# X-DO10_RFID_LED_V1_0_1.net
KiCad netlist of a schematic drawn in Altium Designer
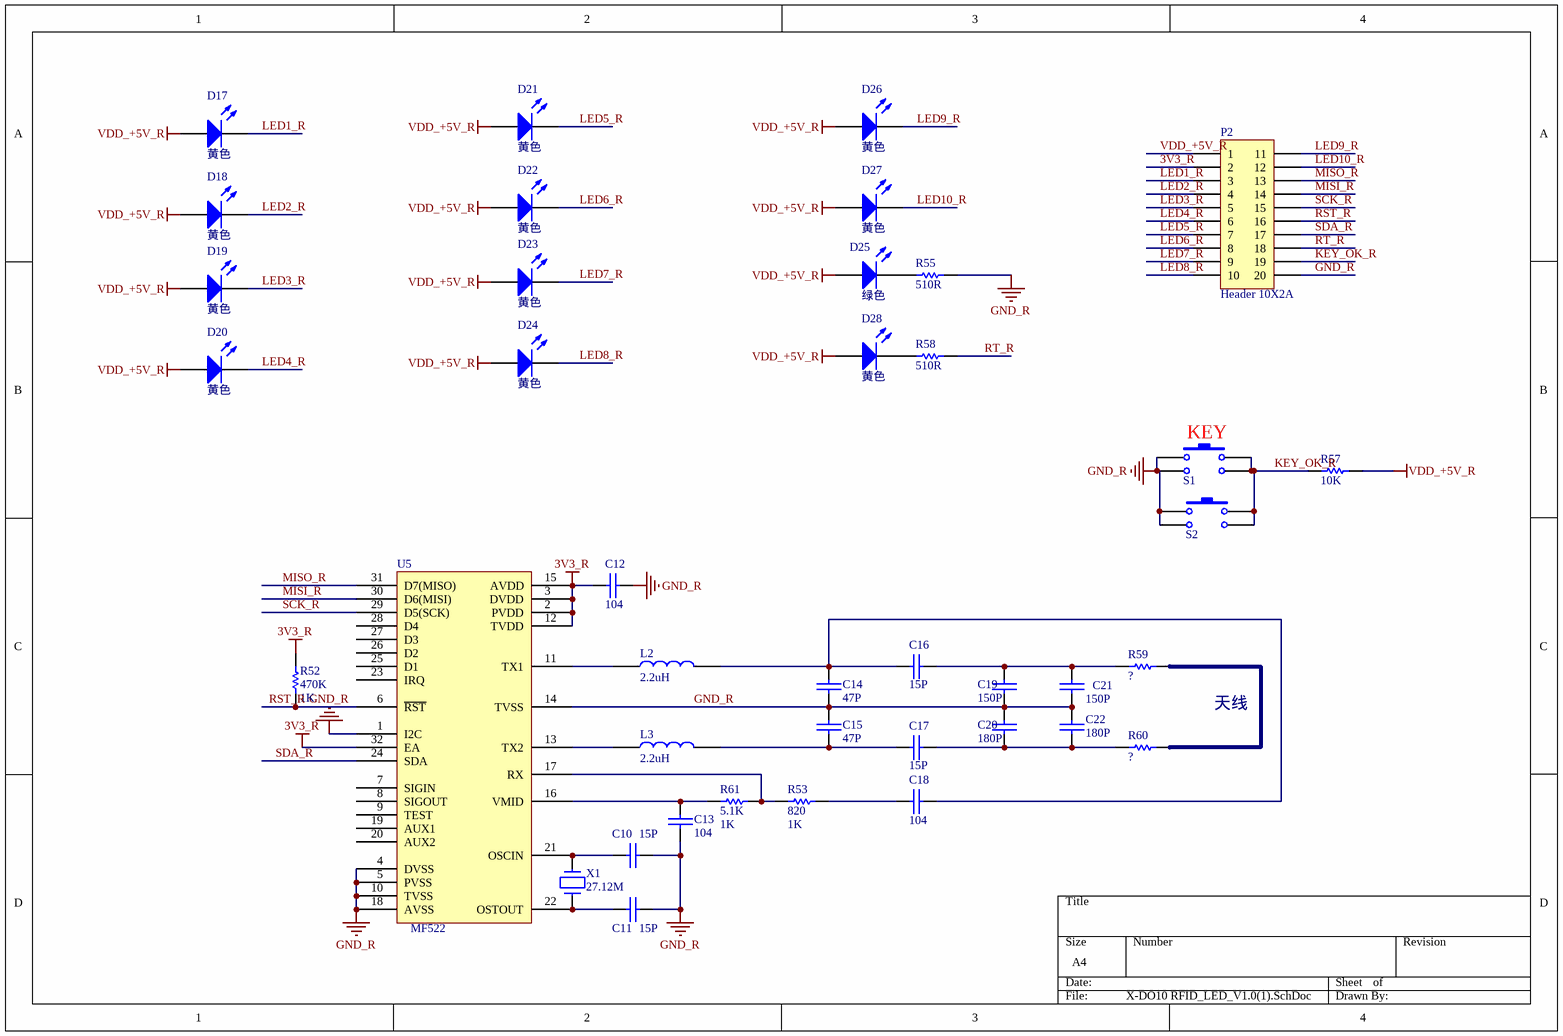
[diagram p0: X-DO10 RFID_LED_V1.0(1).SchDoc]

(export (version "E")
  (design (tool "Eeschema 10.0.6"))
  (components
    (comp (ref "C10")
      (value "15P")
      (footprint "c0603")
      (description "Capacitor")
      (libsource (lib "*") (part "CAP"))
    )
    (comp (ref "C11")
      (value "15P")
      (footprint "c0603")
      (description "Capacitor")
      (libsource (lib "*") (part "CAP"))
    )
    (comp (ref "C12")
      (value "104")
      (footprint "c0603")
      (description "Capacitor")
      (libsource (lib "*") (part "CAP"))
    )
    (comp (ref "C13")
      (value "104")
      (footprint "c0603")
      (description "Capacitor")
      (libsource (lib "*") (part "CAP"))
    )
    (comp (ref "C14")
      (value "47P")
      (footprint "c0603")
      (description "Capacitor")
      (libsource (lib "*") (part "CAP"))
    )
    (comp (ref "C15")
      (value "47P")
      (footprint "c0603")
      (description "Capacitor")
      (libsource (lib "*") (part "CAP"))
    )
    (comp (ref "C16")
      (value "15P")
      (footprint "c0603")
      (description "Capacitor")
      (libsource (lib "*") (part "CAP"))
    )
    (comp (ref "C17")
      (value "15P")
      (footprint "c0603")
      (description "Capacitor")
      (libsource (lib "*") (part "CAP"))
    )
    (comp (ref "C18")
      (value "104")
      (footprint "c0603")
      (description "Capacitor")
      (libsource (lib "*") (part "CAP"))
    )
    (comp (ref "C19")
      (value "150P")
      (footprint "c0603")
      (description "Capacitor")
      (libsource (lib "*") (part "CAP"))
    )
    (comp (ref "C20")
      (value "180P")
      (footprint "c0603")
      (description "Capacitor")
      (libsource (lib "*") (part "CAP"))
    )
    (comp (ref "C21")
      (value "150P")
      (footprint "c0603")
      (description "Capacitor")
      (libsource (lib "*") (part "CAP"))
    )
    (comp (ref "C22")
      (value "180P")
      (footprint "c0603")
      (description "Capacitor")
      (libsource (lib "*") (part "CAP"))
    )
    (comp (ref "D17")
      (value "黄色")
      (footprint "LED-2.54-3")
      (description "Typical INFRARED GaAs LED")
      (fields (field (name "ALTIUM_UNNAMED_1") "黄色"))
      (libsource (lib "*") (part "LED0"))
    )
    (comp (ref "D18")
      (value "黄色")
      (footprint "LED-2.54-3")
      (description "Typical INFRARED GaAs LED")
      (fields (field (name "ALTIUM_UNNAMED_1") "黄色"))
      (libsource (lib "*") (part "LED0"))
    )
    (comp (ref "D19")
      (value "黄色")
      (footprint "LED-2.54-3")
      (description "Typical INFRARED GaAs LED")
      (fields (field (name "ALTIUM_UNNAMED_1") "黄色"))
      (libsource (lib "*") (part "LED0"))
    )
    (comp (ref "D20")
      (value "黄色")
      (footprint "LED-2.54-3")
      (description "Typical INFRARED GaAs LED")
      (fields (field (name "ALTIUM_UNNAMED_1") "黄色"))
      (libsource (lib "*") (part "LED0"))
    )
    (comp (ref "D21")
      (value "黄色")
      (footprint "LED-2.54-3")
      (description "Typical INFRARED GaAs LED")
      (fields (field (name "ALTIUM_UNNAMED_1") "黄色"))
      (libsource (lib "*") (part "LED0"))
    )
    (comp (ref "D22")
      (value "黄色")
      (footprint "LED-2.54-3")
      (description "Typical INFRARED GaAs LED")
      (fields (field (name "ALTIUM_UNNAMED_1") "黄色"))
      (libsource (lib "*") (part "LED0"))
    )
    (comp (ref "D23")
      (value "黄色")
      (footprint "LED-2.54-3")
      (description "Typical INFRARED GaAs LED")
      (fields (field (name "ALTIUM_UNNAMED_1") "黄色"))
      (libsource (lib "*") (part "LED0"))
    )
    (comp (ref "D24")
      (value "黄色")
      (footprint "LED-2.54-3")
      (description "Typical INFRARED GaAs LED")
      (fields (field (name "ALTIUM_UNNAMED_1") "黄色"))
      (libsource (lib "*") (part "LED0"))
    )
    (comp (ref "D25")
      (value "红色")
      (footprint "LED-2.54-3")
      (description "Typical INFRARED GaAs LED")
      (fields (field (name "ALTIUM_UNNAMED_1") "绿色"))
      (libsource (lib "*") (part "LED0"))
    )
    (comp (ref "D26")
      (value "黄色")
      (footprint "LED-2.54-3")
      (description "Typical INFRARED GaAs LED")
      (fields (field (name "ALTIUM_UNNAMED_1") "黄色"))
      (libsource (lib "*") (part "LED0"))
    )
    (comp (ref "D27")
      (value "黄色")
      (footprint "LED-2.54-3")
      (description "Typical INFRARED GaAs LED")
      (fields (field (name "ALTIUM_UNNAMED_1") "黄色"))
      (libsource (lib "*") (part "LED0"))
    )
    (comp (ref "D28")
      (value "红色")
      (footprint "LED-2.54-3")
      (description "Typical INFRARED GaAs LED")
      (fields (field (name "ALTIUM_UNNAMED_1") "黄色"))
      (libsource (lib "*") (part "LED0"))
    )
    (comp (ref "L2") (value "2.2uH") (footprint "r0805") (libsource (lib "*") (part "INDUCTOR1")))
    (comp (ref "L3") (value "2.2uH") (footprint "r0805") (libsource (lib "*") (part "INDUCTOR1")))
    (comp (ref "P2")
      (value "Header 10X2A")
      (footprint "SMT2.0  2*10")
      (description "Header, 10-Pin, Dual row")
      (fields (field (name "PUBLISHER") "Altium Limited"))
      (libsource (lib "Miscellaneous Connectors") (part "Header 10X2A"))
    )
    (comp (ref "R52")
      (value "470K")
      (footprint "R0603")
      (description "Semiconductor Resistor")
      (fields (field (name "ALTIUM_VALUE") "1K") (field (name "PUBLISHER") "Altium Limited"))
      (libsource (lib "Miscellaneous Devices") (part "Res Semi"))
    )
    (comp (ref "R53")
      (value "820")
      (footprint "r0603")
      (description "Semiconductor Resistor")
      (fields (field (name "ALTIUM_VALUE") "1K") (field (name "PUBLISHER") "Altium Limited"))
      (libsource (lib "Miscellaneous Devices") (part "Res Semi"))
    )
    (comp (ref "R55")
      (value "贴片电阻")
      (footprint "R0603")
      (description "Semiconductor Resistor")
      (fields (field (name "ALTIUM_UNNAMED_1") "510R"))
      (libsource (lib "Miscellaneous Devices") (part "Res Semi"))
    )
    (comp (ref "R57")
      (value "~")
      (footprint "R0603")
      (description "Semiconductor Resistor")
      (fields (field (name "ALTIUM_UNNAMED_1") "10K"))
      (libsource (lib "Miscellaneous Devices") (part "Res Semi"))
    )
    (comp (ref "R58")
      (value "~")
      (footprint "R0603")
      (description "Semiconductor Resistor")
      (fields (field (name "ALTIUM_UNNAMED_1") "510R"))
      (libsource (lib "Miscellaneous Devices") (part "Res Semi"))
    )
    (comp (ref "R59")
      (value "?")
      (footprint "R0805")
      (description "Semiconductor Resistor")
      (fields (field (name "PUBLISHER") "Altium Limited"))
      (libsource (lib "Miscellaneous Devices") (part "Res Semi"))
    )
    (comp (ref "R60")
      (value "?")
      (footprint "R0805")
      (description "Semiconductor Resistor")
      (fields (field (name "PUBLISHER") "Altium Limited"))
      (libsource (lib "Miscellaneous Devices") (part "Res Semi"))
    )
    (comp (ref "R61")
      (value "5.1K")
      (footprint "r0603")
      (description "Semiconductor Resistor")
      (fields (field (name "ALTIUM_VALUE") "1K") (field (name "PUBLISHER") "Altium Limited"))
      (libsource (lib "Miscellaneous Devices") (part "Res Semi"))
    )
    (comp (ref "S1") (value "TS1102W") (footprint "TS1102W") (libsource (lib "MODBUS_V1.0") (part "TS1102W")))
    (comp (ref "S2") (value "TS1102W") (footprint "TS1102W") (libsource (lib "MODBUS_V1.0") (part "TS1102W")))
    (comp (ref "U5")
      (value "MF522")
      (footprint "QFN50P500X500X100-32N")
      (libsource (lib "*") (part "MF522B"))
    )
    (comp (ref "X1") (value "27.12M") (footprint "49US") (libsource (lib "*") (part "Tm08B.S01_12M_42")))
  )
  (nets
    (net (code "1") (name "/KEY_OK_R") (class "Default")
      (node (ref "P2") (pin "19") (pinfunction "19_19") (pintype "passive"))
      (node (ref "R57") (pin "2") (pinfunction "2_2") (pintype "passive"))
      (node (ref "S1") (pin "2") (pinfunction "2_2") (pintype "passive"))
      (node (ref "S1") (pin "4") (pinfunction "4_4") (pintype "passive"))
      (node (ref "S2") (pin "2") (pinfunction "2_2") (pintype "passive"))
      (node (ref "S2") (pin "4") (pinfunction "4_4") (pintype "passive"))
    )
    (net (code "2") (name "/LED1_R") (class "Default")
      (node (ref "D17") (pin "2") (pinfunction "K_2") (pintype "passive"))
      (node (ref "P2") (pin "3") (pinfunction "3_3") (pintype "passive"))
    )
    (net (code "3") (name "/LED2_R") (class "Default")
      (node (ref "D18") (pin "2") (pinfunction "K_2") (pintype "passive"))
      (node (ref "P2") (pin "4") (pinfunction "4_4") (pintype "passive"))
    )
    (net (code "4") (name "/LED3_R") (class "Default")
      (node (ref "D19") (pin "2") (pinfunction "K_2") (pintype "passive"))
      (node (ref "P2") (pin "5") (pinfunction "5_5") (pintype "passive"))
    )
    (net (code "5") (name "/LED4_R") (class "Default")
      (node (ref "D20") (pin "2") (pinfunction "K_2") (pintype "passive"))
      (node (ref "P2") (pin "6") (pinfunction "6_6") (pintype "passive"))
    )
    (net (code "6") (name "/LED5_R") (class "Default")
      (node (ref "D21") (pin "2") (pinfunction "K_2") (pintype "passive"))
      (node (ref "P2") (pin "7") (pinfunction "7_7") (pintype "passive"))
    )
    (net (code "7") (name "/LED6_R") (class "Default")
      (node (ref "D22") (pin "2") (pinfunction "K_2") (pintype "passive"))
      (node (ref "P2") (pin "8") (pinfunction "8_8") (pintype "passive"))
    )
    (net (code "8") (name "/LED7_R") (class "Default")
      (node (ref "D23") (pin "2") (pinfunction "K_2") (pintype "passive"))
      (node (ref "P2") (pin "9") (pinfunction "9_9") (pintype "passive"))
    )
    (net (code "9") (name "/LED8_R") (class "Default")
      (node (ref "D24") (pin "2") (pinfunction "K_2") (pintype "passive"))
      (node (ref "P2") (pin "10") (pinfunction "10_10") (pintype "passive"))
    )
    (net (code "10") (name "/LED9_R") (class "Default")
      (node (ref "D26") (pin "2") (pinfunction "K_2") (pintype "passive"))
      (node (ref "P2") (pin "11") (pinfunction "11_11") (pintype "passive"))
    )
    (net (code "11") (name "/LED10_R") (class "Default")
      (node (ref "D27") (pin "2") (pinfunction "K_2") (pintype "passive"))
      (node (ref "P2") (pin "12") (pinfunction "12_12") (pintype "passive"))
    )
    (net (code "12") (name "/MISI_R") (class "Default")
      (node (ref "P2") (pin "14") (pinfunction "14_14") (pintype "passive"))
      (node (ref "U5") (pin "30") (pinfunction "D6(MISI)_30") (pintype "passive"))
    )
    (net (code "13") (name "/MISO_R") (class "Default")
      (node (ref "P2") (pin "13") (pinfunction "13_13") (pintype "passive"))
      (node (ref "U5") (pin "31") (pinfunction "D7(MISO)_31") (pintype "passive"))
    )
    (net (code "14") (name "/RST_R") (class "Default")
      (node (ref "P2") (pin "16") (pinfunction "16_16") (pintype "passive"))
      (node (ref "R52") (pin "1") (pinfunction "1_1") (pintype "passive"))
      (node (ref "U5") (pin "6") (pinfunction "~{RST}_6") (pintype "passive"))
    )
    (net (code "15") (name "/RT_R") (class "Default")
      (node (ref "P2") (pin "18") (pinfunction "18_18") (pintype "passive"))
      (node (ref "R58") (pin "1") (pinfunction "1_1") (pintype "passive"))
    )
    (net (code "16") (name "/SCK_R") (class "Default")
      (node (ref "P2") (pin "15") (pinfunction "15_15") (pintype "passive"))
      (node (ref "U5") (pin "29") (pinfunction "D5(SCK)_29") (pintype "passive"))
    )
    (net (code "17") (name "/SDA_R") (class "Default")
      (node (ref "P2") (pin "17") (pinfunction "17_17") (pintype "passive"))
      (node (ref "U5") (pin "24") (pinfunction "SDA_24") (pintype "passive"))
    )
    (net (code "18") (name "3V3_R") (class "Default")
      (node (ref "C12") (pin "1") (pinfunction "1_1") (pintype "passive"))
      (node (ref "P2") (pin "2") (pinfunction "2_2") (pintype "passive"))
      (node (ref "R52") (pin "2") (pinfunction "2_2") (pintype "passive"))
      (node (ref "U5") (pin "12") (pinfunction "TVDD_12") (pintype "power_in"))
      (node (ref "U5") (pin "15") (pinfunction "AVDD_15") (pintype "power_in"))
      (node (ref "U5") (pin "2") (pinfunction "PVDD_2") (pintype "power_in"))
      (node (ref "U5") (pin "3") (pinfunction "DVDD_3") (pintype "passive"))
      (node (ref "U5") (pin "32") (pinfunction "EA_32") (pintype "passive"))
    )
    (net (code "19") (name "GND_R") (class "Default")
      (node (ref "C10") (pin "2") (pinfunction "2_2") (pintype "passive"))
      (node (ref "C11") (pin "2") (pinfunction "2_2") (pintype "passive"))
      (node (ref "C12") (pin "2") (pinfunction "2_2") (pintype "passive"))
      (node (ref "C13") (pin "2") (pinfunction "2_2") (pintype "passive"))
      (node (ref "C14") (pin "1") (pinfunction "1_1") (pintype "passive"))
      (node (ref "C15") (pin "1") (pinfunction "1_1") (pintype "passive"))
      (node (ref "C19") (pin "2") (pinfunction "2_2") (pintype "passive"))
      (node (ref "C20") (pin "1") (pinfunction "1_1") (pintype "passive"))
      (node (ref "C21") (pin "2") (pinfunction "2_2") (pintype "passive"))
      (node (ref "C22") (pin "1") (pinfunction "1_1") (pintype "passive"))
      (node (ref "P2") (pin "20") (pinfunction "20_20") (pintype "passive"))
      (node (ref "R55") (pin "1") (pinfunction "1_1") (pintype "passive"))
      (node (ref "S1") (pin "1") (pinfunction "1_1") (pintype "passive"))
      (node (ref "S1") (pin "3") (pinfunction "3_3") (pintype "passive"))
      (node (ref "S2") (pin "1") (pinfunction "1_1") (pintype "passive"))
      (node (ref "S2") (pin "3") (pinfunction "3_3") (pintype "passive"))
      (node (ref "U5") (pin "1") (pinfunction "I2C_1") (pintype "passive"))
      (node (ref "U5") (pin "10") (pinfunction "TVSS_10") (pintype "passive"))
      (node (ref "U5") (pin "14") (pinfunction "TVSS_14") (pintype "passive"))
      (node (ref "U5") (pin "18") (pinfunction "AVSS_18") (pintype "passive"))
      (node (ref "U5") (pin "4") (pinfunction "DVSS_4") (pintype "passive"))
      (node (ref "U5") (pin "5") (pinfunction "PVSS_5") (pintype "passive"))
    )
    (net (code "20") (name "Net-(C14-Pad2)") (class "Default")
      (node (ref "C14") (pin "2") (pinfunction "2_2") (pintype "passive"))
      (node (ref "C16") (pin "2") (pinfunction "2_2") (pintype "passive"))
      (node (ref "C18") (pin "2") (pinfunction "2_2") (pintype "passive"))
      (node (ref "L2") (pin "2") (pinfunction "2_2") (pintype "passive"))
    )
    (net (code "21") (name "Net-(C15-Pad2)") (class "Default")
      (node (ref "C15") (pin "2") (pinfunction "2_2") (pintype "passive"))
      (node (ref "C17") (pin "2") (pinfunction "2_2") (pintype "passive"))
      (node (ref "L3") (pin "2") (pinfunction "2_2") (pintype "passive"))
    )
    (net (code "22") (name "Net-(C16-Pad1)") (class "Default")
      (node (ref "C16") (pin "1") (pinfunction "1_1") (pintype "passive"))
      (node (ref "C19") (pin "1") (pinfunction "1_1") (pintype "passive"))
      (node (ref "C21") (pin "1") (pinfunction "1_1") (pintype "passive"))
      (node (ref "R59") (pin "1") (pinfunction "1_1") (pintype "passive"))
    )
    (net (code "23") (name "Net-(C17-Pad1)") (class "Default")
      (node (ref "C17") (pin "1") (pinfunction "1_1") (pintype "passive"))
      (node (ref "C20") (pin "2") (pinfunction "2_2") (pintype "passive"))
      (node (ref "C22") (pin "2") (pinfunction "2_2") (pintype "passive"))
      (node (ref "R60") (pin "1") (pinfunction "1_1") (pintype "passive"))
    )
    (net (code "24") (name "Net-(C18-Pad1)") (class "Default")
      (node (ref "C18") (pin "1") (pinfunction "1_1") (pintype "passive"))
      (node (ref "R53") (pin "2") (pinfunction "2_2") (pintype "passive"))
    )
    (net (code "25") (name "Net-(D25-K)") (class "Default")
      (node (ref "D25") (pin "2") (pinfunction "K_2") (pintype "passive"))
      (node (ref "R55") (pin "2") (pinfunction "2_2") (pintype "passive"))
    )
    (net (code "26") (name "Net-(D28-K)") (class "Default")
      (node (ref "D28") (pin "2") (pinfunction "K_2") (pintype "passive"))
      (node (ref "R58") (pin "2") (pinfunction "2_2") (pintype "passive"))
    )
    (net (code "27") (name "Net-(R59-Pad2)") (class "Default")
      (node (ref "R59") (pin "2") (pinfunction "2_2") (pintype "passive"))
      (node (ref "R60") (pin "2") (pinfunction "2_2") (pintype "passive"))
    )
    (net (code "28") (name "Net-(U5-OSCIN)") (class "Default")
      (node (ref "C10") (pin "1") (pinfunction "1_1") (pintype "passive"))
      (node (ref "U5") (pin "21") (pinfunction "OSCIN_21") (pintype "passive"))
      (node (ref "X1") (pin "2") (pintype "passive"))
    )
    (net (code "29") (name "Net-(U5-OSTOUT)") (class "Default")
      (node (ref "C11") (pin "1") (pinfunction "1_1") (pintype "passive"))
      (node (ref "U5") (pin "22") (pinfunction "OSTOUT_22") (pintype "passive"))
      (node (ref "X1") (pin "1") (pintype "passive"))
    )
    (net (code "30") (name "Net-(U5-RX)") (class "Default")
      (node (ref "R53") (pin "1") (pinfunction "1_1") (pintype "passive"))
      (node (ref "R61") (pin "2") (pinfunction "2_2") (pintype "passive"))
      (node (ref "U5") (pin "17") (pinfunction "RX_17") (pintype "passive"))
    )
    (net (code "31") (name "Net-(U5-TX1)") (class "Default")
      (node (ref "L2") (pin "1") (pinfunction "1_1") (pintype "passive"))
      (node (ref "U5") (pin "11") (pinfunction "TX1_11") (pintype "passive"))
    )
    (net (code "32") (name "Net-(U5-TX2)") (class "Default")
      (node (ref "L3") (pin "1") (pinfunction "1_1") (pintype "passive"))
      (node (ref "U5") (pin "13") (pinfunction "TX2_13") (pintype "passive"))
    )
    (net (code "33") (name "Net-(U5-VMID)") (class "Default")
      (node (ref "C13") (pin "1") (pinfunction "1_1") (pintype "passive"))
      (node (ref "R61") (pin "1") (pinfunction "1_1") (pintype "passive"))
      (node (ref "U5") (pin "16") (pinfunction "VMID_16") (pintype "passive"))
    )
    (net (code "34") (name "VDD_+5V_R") (class "Default")
      (node (ref "D17") (pin "1") (pinfunction "A_1") (pintype "passive"))
      (node (ref "D18") (pin "1") (pinfunction "A_1") (pintype "passive"))
      (node (ref "D19") (pin "1") (pinfunction "A_1") (pintype "passive"))
      (node (ref "D20") (pin "1") (pinfunction "A_1") (pintype "passive"))
      (node (ref "D21") (pin "1") (pinfunction "A_1") (pintype "passive"))
      (node (ref "D22") (pin "1") (pinfunction "A_1") (pintype "passive"))
      (node (ref "D23") (pin "1") (pinfunction "A_1") (pintype "passive"))
      (node (ref "D24") (pin "1") (pinfunction "A_1") (pintype "passive"))
      (node (ref "D25") (pin "1") (pinfunction "A_1") (pintype "passive"))
      (node (ref "D26") (pin "1") (pinfunction "A_1") (pintype "passive"))
      (node (ref "D27") (pin "1") (pinfunction "A_1") (pintype "passive"))
      (node (ref "D28") (pin "1") (pinfunction "A_1") (pintype "passive"))
      (node (ref "P2") (pin "1") (pinfunction "1_1") (pintype "passive"))
      (node (ref "R57") (pin "1") (pinfunction "1_1") (pintype "passive"))
    )
    (net (code "35") (name "unconnected-(U5-AUX1-Pad19)") (class "Default")
      (node (ref "U5") (pin "19") (pinfunction "AUX1_19") (pintype "passive"))
    )
    (net (code "36") (name "unconnected-(U5-AUX2-Pad20)") (class "Default")
      (node (ref "U5") (pin "20") (pinfunction "AUX2_20") (pintype "passive"))
    )
    (net (code "37") (name "unconnected-(U5-D1-Pad25)") (class "Default")
      (node (ref "U5") (pin "25") (pinfunction "D1_25") (pintype "passive"))
    )
    (net (code "38") (name "unconnected-(U5-D2-Pad26)") (class "Default")
      (node (ref "U5") (pin "26") (pinfunction "D2_26") (pintype "passive"))
    )
    (net (code "39") (name "unconnected-(U5-D3-Pad27)") (class "Default")
      (node (ref "U5") (pin "27") (pinfunction "D3_27") (pintype "passive"))
    )
    (net (code "40") (name "unconnected-(U5-D4-Pad28)") (class "Default")
      (node (ref "U5") (pin "28") (pinfunction "D4_28") (pintype "passive"))
    )
    (net (code "41") (name "unconnected-(U5-IRQ-Pad23)") (class "Default")
      (node (ref "U5") (pin "23") (pinfunction "IRQ_23") (pintype "passive"))
    )
    (net (code "42") (name "unconnected-(U5-SIGIN-Pad7)") (class "Default")
      (node (ref "U5") (pin "7") (pinfunction "SIGIN_7") (pintype "passive"))
    )
    (net (code "43") (name "unconnected-(U5-SIGOUT-Pad8)") (class "Default")
      (node (ref "U5") (pin "8") (pinfunction "SIGOUT_8") (pintype "passive"))
    )
    (net (code "44") (name "unconnected-(U5-TEST-Pad9)") (class "Default")
      (node (ref "U5") (pin "9") (pinfunction "TEST_9") (pintype "passive"))
    )
  )
)
